# dac-eval-simplified.net
KiCad netlist of a schematic drawn in EAGLE
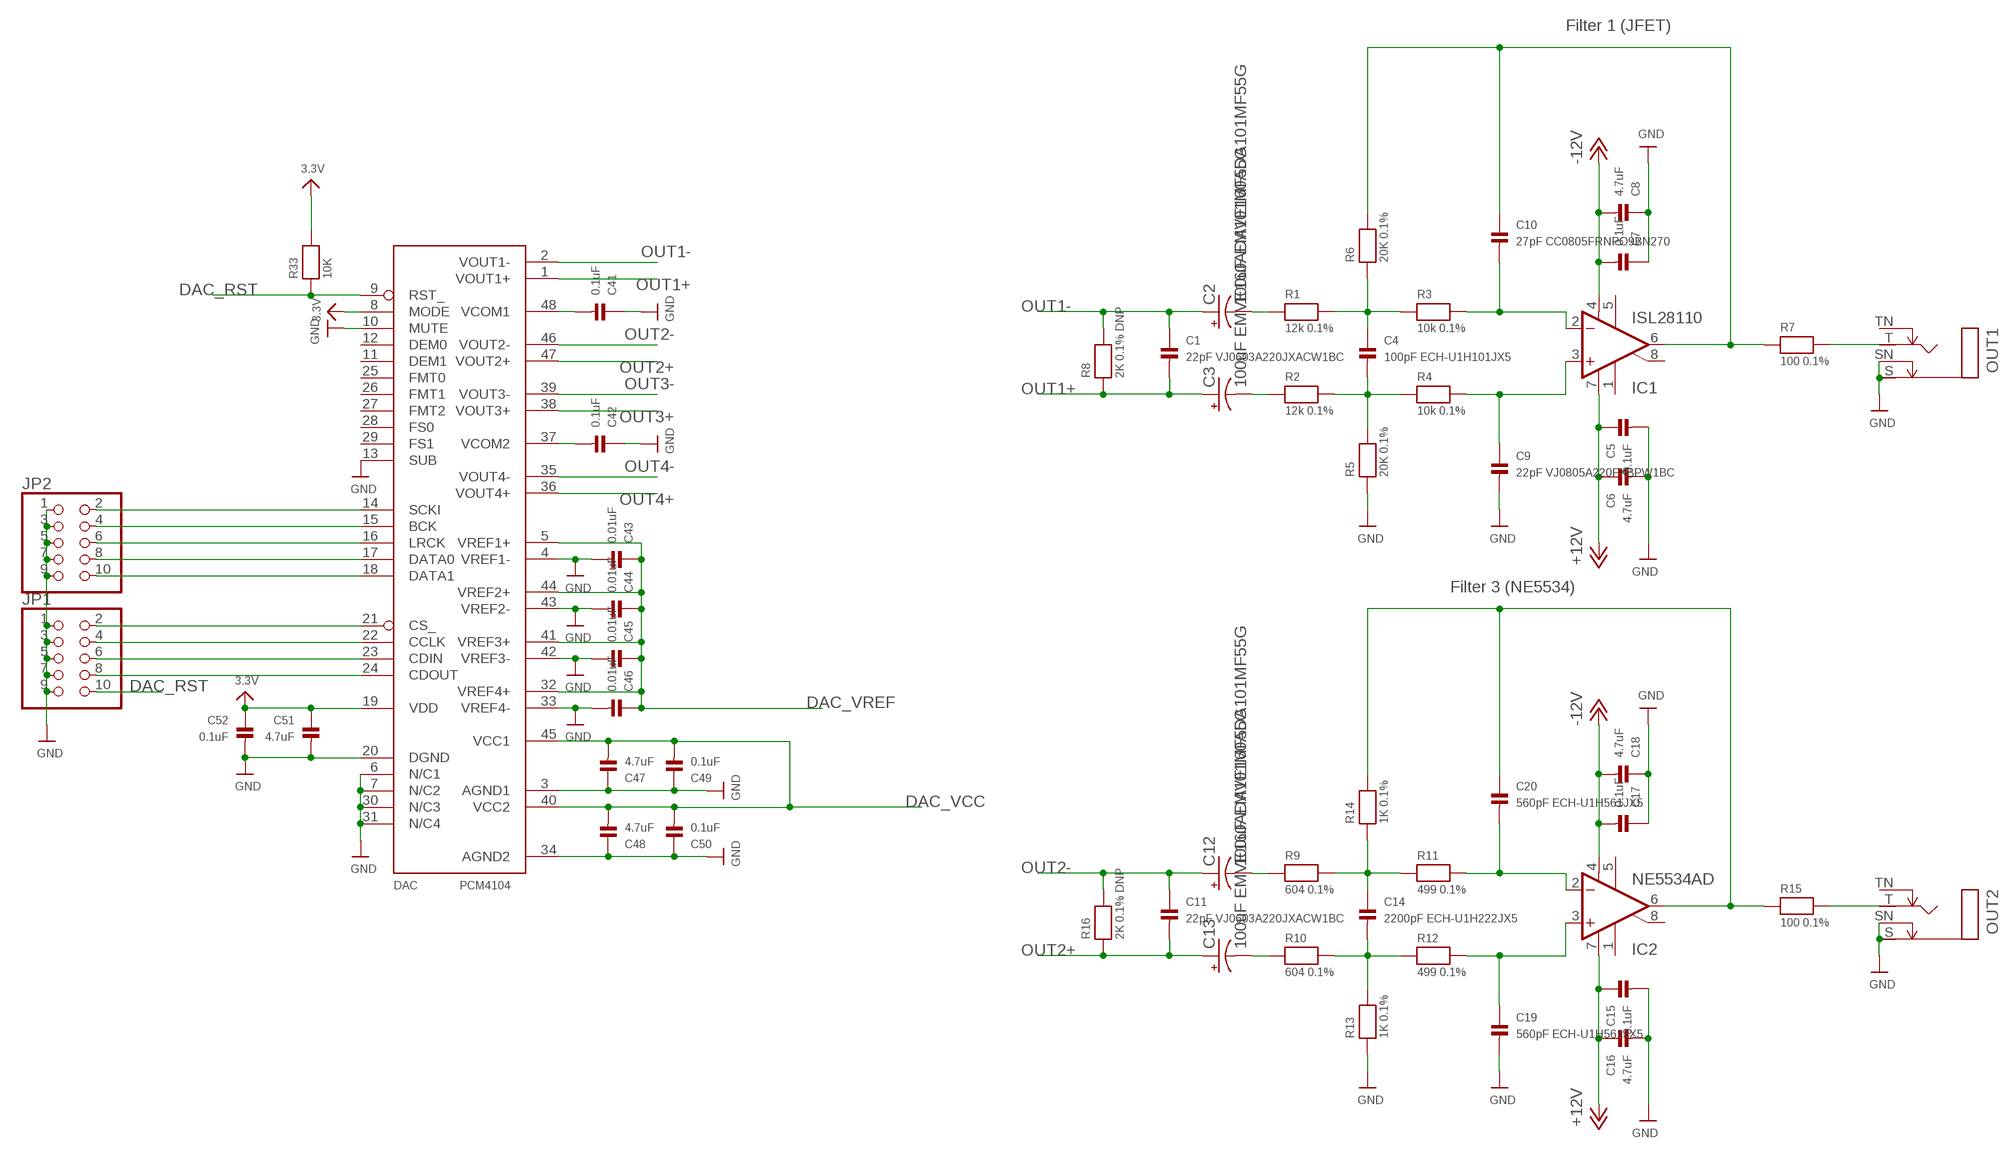
[diagram p0: schematic, sheet 1, part 1 of 2]
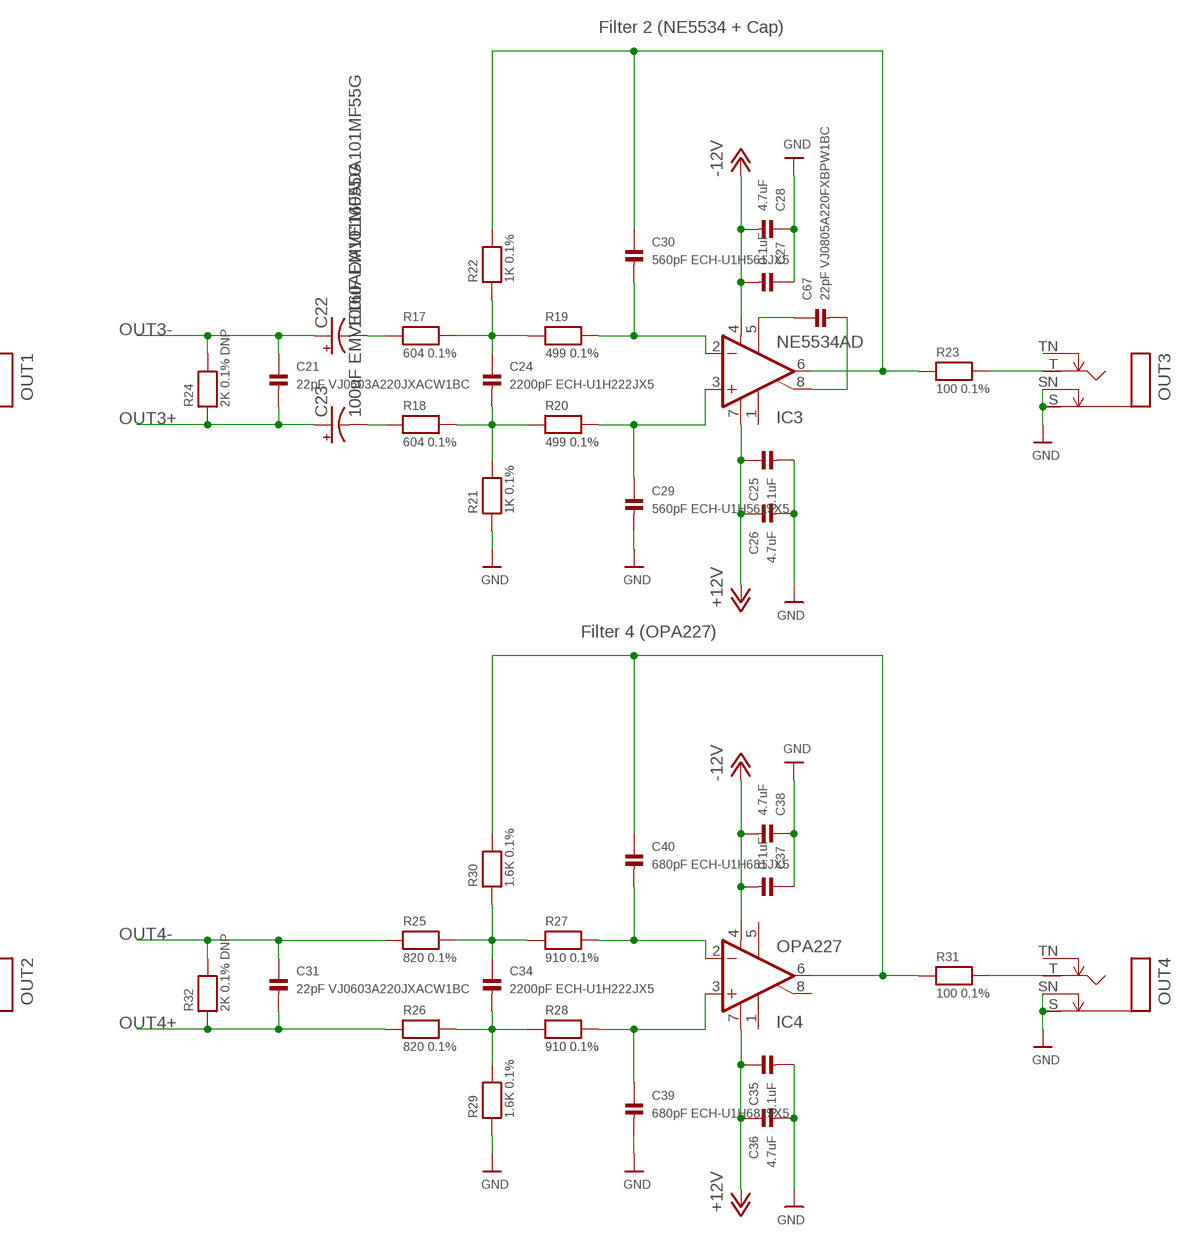
[diagram p1: schematic, sheet 1, part 2 of 2]
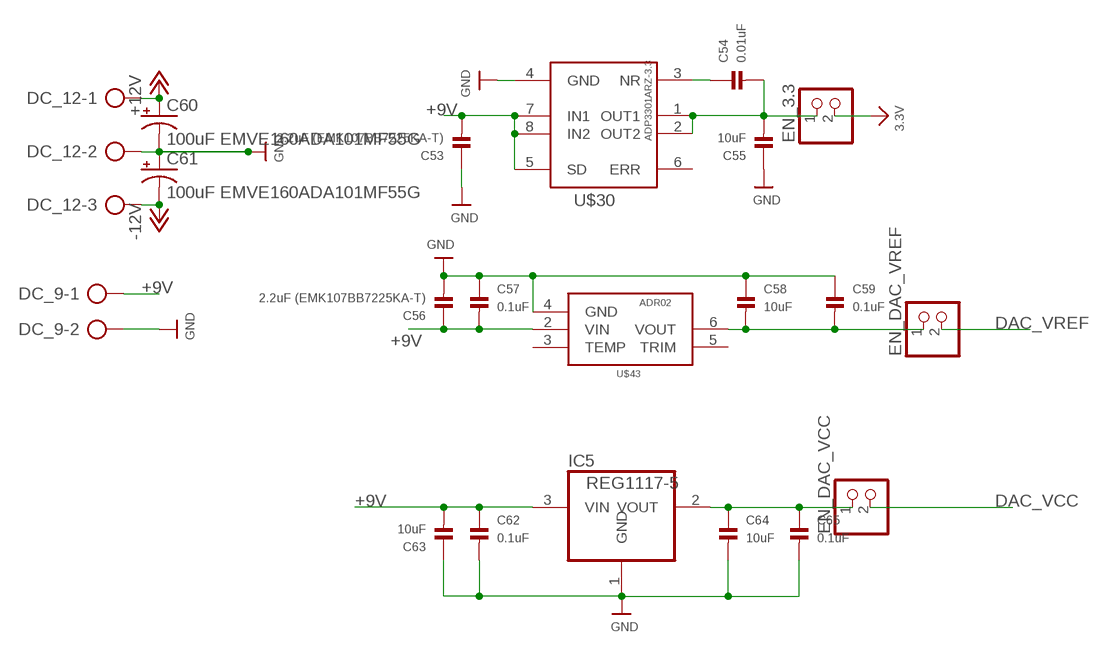
[diagram p2: schematic, sheet 2]

(export (version "E")
  (design (tool "Eeschema 10.0.6"))
  (components
    (comp (ref "C1")
      (value "22pF VJ0603A220JXACW1BC")
      (footprint "eagle-import:0603")
      (libsource (lib "eagle-import") (part "CAP_CERAMIC0603"))
    )
    (comp (ref "C2")
      (value "100uF EMVE160ADA101MF55G")
      (footprint "eagle-import:PANASONIC_D")
      (libsource (lib "eagle-import") (part "CAP_POLD"))
    )
    (comp (ref "C3")
      (value "100uF EMVE160ADA101MF55G")
      (footprint "eagle-import:PANASONIC_D")
      (libsource (lib "eagle-import") (part "CAP_POLD"))
    )
    (comp (ref "C4")
      (value "100pF ECH-U1H101JX5")
      (footprint "eagle-import:0805")
      (libsource (lib "eagle-import") (part "CAP_CERAMIC0805"))
    )
    (comp (ref "C5")
      (value "0.1uF")
      (footprint "eagle-import:0603")
      (libsource (lib "eagle-import") (part "CAP_CERAMIC0603"))
    )
    (comp (ref "C6")
      (value "4.7uF")
      (footprint "eagle-import:0603")
      (libsource (lib "eagle-import") (part "CAP_CERAMIC0603"))
    )
    (comp (ref "C7")
      (value "0.1uF")
      (footprint "eagle-import:0603")
      (libsource (lib "eagle-import") (part "CAP_CERAMIC0603"))
    )
    (comp (ref "C8")
      (value "4.7uF")
      (footprint "eagle-import:0603")
      (libsource (lib "eagle-import") (part "CAP_CERAMIC0603"))
    )
    (comp (ref "C9")
      (value "22pF VJ0805A220FXBPW1BC")
      (footprint "eagle-import:0805")
      (libsource (lib "eagle-import") (part "CAP_CERAMIC0805"))
    )
    (comp (ref "C10")
      (value "27pF CC0805FRNPO9BN270")
      (footprint "eagle-import:0805")
      (libsource (lib "eagle-import") (part "CAP_CERAMIC0805"))
    )
    (comp (ref "C11")
      (value "22pF VJ0603A220JXACW1BC")
      (footprint "eagle-import:0603")
      (libsource (lib "eagle-import") (part "CAP_CERAMIC0603"))
    )
    (comp (ref "C12")
      (value "100uF EMVE160ADA101MF55G")
      (footprint "eagle-import:PANASONIC_D")
      (libsource (lib "eagle-import") (part "CAP_POLD"))
    )
    (comp (ref "C13")
      (value "100uF EMVE160ADA101MF55G")
      (footprint "eagle-import:PANASONIC_D")
      (libsource (lib "eagle-import") (part "CAP_POLD"))
    )
    (comp (ref "C14")
      (value "2200pF ECH-U1H222JX5")
      (footprint "eagle-import:0805")
      (libsource (lib "eagle-import") (part "CAP_CERAMIC0805"))
    )
    (comp (ref "C15")
      (value "0.1uF")
      (footprint "eagle-import:0603")
      (libsource (lib "eagle-import") (part "CAP_CERAMIC0603"))
    )
    (comp (ref "C16")
      (value "4.7uF")
      (footprint "eagle-import:0603")
      (libsource (lib "eagle-import") (part "CAP_CERAMIC0603"))
    )
    (comp (ref "C17")
      (value "0.1uF")
      (footprint "eagle-import:0603")
      (libsource (lib "eagle-import") (part "CAP_CERAMIC0603"))
    )
    (comp (ref "C18")
      (value "4.7uF")
      (footprint "eagle-import:0603")
      (libsource (lib "eagle-import") (part "CAP_CERAMIC0603"))
    )
    (comp (ref "C19")
      (value "560pF ECH-U1H561JX5")
      (footprint "eagle-import:0805")
      (libsource (lib "eagle-import") (part "CAP_CERAMIC0805"))
    )
    (comp (ref "C20")
      (value "560pF ECH-U1H561JX5")
      (footprint "eagle-import:0805")
      (libsource (lib "eagle-import") (part "CAP_CERAMIC0805"))
    )
    (comp (ref "C21")
      (value "22pF VJ0603A220JXACW1BC")
      (footprint "eagle-import:0603")
      (libsource (lib "eagle-import") (part "CAP_CERAMIC0603"))
    )
    (comp (ref "C22")
      (value "100uF EMVE160ADA101MF55G")
      (footprint "eagle-import:PANASONIC_D")
      (libsource (lib "eagle-import") (part "CAP_POLD"))
    )
    (comp (ref "C23")
      (value "100uF EMVE160ADA101MF55G")
      (footprint "eagle-import:PANASONIC_D")
      (libsource (lib "eagle-import") (part "CAP_POLD"))
    )
    (comp (ref "C24")
      (value "2200pF ECH-U1H222JX5")
      (footprint "eagle-import:0805")
      (libsource (lib "eagle-import") (part "CAP_CERAMIC0805"))
    )
    (comp (ref "C25")
      (value "0.1uF")
      (footprint "eagle-import:0603")
      (libsource (lib "eagle-import") (part "CAP_CERAMIC0603"))
    )
    (comp (ref "C26")
      (value "4.7uF")
      (footprint "eagle-import:0603")
      (libsource (lib "eagle-import") (part "CAP_CERAMIC0603"))
    )
    (comp (ref "C27")
      (value "0.1uF")
      (footprint "eagle-import:0603")
      (libsource (lib "eagle-import") (part "CAP_CERAMIC0603"))
    )
    (comp (ref "C28")
      (value "4.7uF")
      (footprint "eagle-import:0603")
      (libsource (lib "eagle-import") (part "CAP_CERAMIC0603"))
    )
    (comp (ref "C29")
      (value "560pF ECH-U1H561JX5")
      (footprint "eagle-import:0805")
      (libsource (lib "eagle-import") (part "CAP_CERAMIC0805"))
    )
    (comp (ref "C30")
      (value "560pF ECH-U1H561JX5")
      (footprint "eagle-import:0805")
      (libsource (lib "eagle-import") (part "CAP_CERAMIC0805"))
    )
    (comp (ref "C31")
      (value "22pF VJ0603A220JXACW1BC")
      (footprint "eagle-import:0603")
      (libsource (lib "eagle-import") (part "CAP_CERAMIC0603"))
    )
    (comp (ref "C34")
      (value "2200pF ECH-U1H222JX5")
      (footprint "eagle-import:0805")
      (libsource (lib "eagle-import") (part "CAP_CERAMIC0805"))
    )
    (comp (ref "C35")
      (value "0.1uF")
      (footprint "eagle-import:0603")
      (libsource (lib "eagle-import") (part "CAP_CERAMIC0603"))
    )
    (comp (ref "C36")
      (value "4.7uF")
      (footprint "eagle-import:0603")
      (libsource (lib "eagle-import") (part "CAP_CERAMIC0603"))
    )
    (comp (ref "C37")
      (value "0.1uF")
      (footprint "eagle-import:0603")
      (libsource (lib "eagle-import") (part "CAP_CERAMIC0603"))
    )
    (comp (ref "C38")
      (value "4.7uF")
      (footprint "eagle-import:0603")
      (libsource (lib "eagle-import") (part "CAP_CERAMIC0603"))
    )
    (comp (ref "C39")
      (value "680pF ECH-U1H681JX5")
      (footprint "eagle-import:0805")
      (libsource (lib "eagle-import") (part "CAP_CERAMIC0805"))
    )
    (comp (ref "C40")
      (value "680pF ECH-U1H681JX5")
      (footprint "eagle-import:0805")
      (libsource (lib "eagle-import") (part "CAP_CERAMIC0805"))
    )
    (comp (ref "C41")
      (value "0.1uF")
      (footprint "eagle-import:0603")
      (libsource (lib "eagle-import") (part "CAP_CERAMIC0603"))
    )
    (comp (ref "C42")
      (value "0.1uF")
      (footprint "eagle-import:0603")
      (libsource (lib "eagle-import") (part "CAP_CERAMIC0603"))
    )
    (comp (ref "C43")
      (value "0.01uF")
      (footprint "eagle-import:0603")
      (libsource (lib "eagle-import") (part "CAP_CERAMIC0603"))
    )
    (comp (ref "C44")
      (value "0.01uF")
      (footprint "eagle-import:0603")
      (libsource (lib "eagle-import") (part "CAP_CERAMIC0603"))
    )
    (comp (ref "C45")
      (value "0.01uF")
      (footprint "eagle-import:0603")
      (libsource (lib "eagle-import") (part "CAP_CERAMIC0603"))
    )
    (comp (ref "C46")
      (value "0.01uF")
      (footprint "eagle-import:0603")
      (libsource (lib "eagle-import") (part "CAP_CERAMIC0603"))
    )
    (comp (ref "C47")
      (value "4.7uF")
      (footprint "eagle-import:0603")
      (libsource (lib "eagle-import") (part "CAP_CERAMIC0603"))
    )
    (comp (ref "C48")
      (value "4.7uF")
      (footprint "eagle-import:0603")
      (libsource (lib "eagle-import") (part "CAP_CERAMIC0603"))
    )
    (comp (ref "C49")
      (value "0.1uF")
      (footprint "eagle-import:0603")
      (libsource (lib "eagle-import") (part "CAP_CERAMIC0603"))
    )
    (comp (ref "C50")
      (value "0.1uF")
      (footprint "eagle-import:0603")
      (libsource (lib "eagle-import") (part "CAP_CERAMIC0603"))
    )
    (comp (ref "C51")
      (value "4.7uF")
      (footprint "eagle-import:0603")
      (libsource (lib "eagle-import") (part "CAP_CERAMIC0603"))
    )
    (comp (ref "C52")
      (value "0.1uF")
      (footprint "eagle-import:0603")
      (libsource (lib "eagle-import") (part "CAP_CERAMIC0603"))
    )
    (comp (ref "C67")
      (value "22pF VJ0805A220FXBPW1BC")
      (footprint "eagle-import:0805")
      (libsource (lib "eagle-import") (part "CAP_CERAMIC0805"))
    )
    (comp (ref "DAC")
      (value "PCM4104")
      (footprint "eagle-import:SQFP-S-7X7-48")
      (libsource (lib "eagle-import") (part "PCM4104"))
    )
    (comp (ref "IC1")
      (value "ISL28110")
      (footprint "eagle-import:SO08")
      (libsource (lib "eagle-import") (part "NE5534DA"))
    )
    (comp (ref "IC2")
      (value "NE5534AD")
      (footprint "eagle-import:SO08")
      (libsource (lib "eagle-import") (part "NE5534DA"))
    )
    (comp (ref "IC3")
      (value "NE5534AD")
      (footprint "eagle-import:SO08")
      (libsource (lib "eagle-import") (part "NE5534DA"))
    )
    (comp (ref "IC4")
      (value "OPA227")
      (footprint "eagle-import:SO08")
      (libsource (lib "eagle-import") (part "NE5534DA"))
    )
    (comp (ref "JP1")
      (value "HEADER-2X5")
      (footprint "eagle-import:2X05")
      (libsource (lib "eagle-import") (part "HEADER-2X5"))
    )
    (comp (ref "JP2")
      (value "HEADER-2X5")
      (footprint "eagle-import:2X05")
      (libsource (lib "eagle-import") (part "HEADER-2X5"))
    )
    (comp (ref "OUT1")
      (value "NMJ4HFD2")
      (footprint "eagle-import:NMJ4HC-S")
      (libsource (lib "eagle-import") (part "MONOSWS"))
    )
    (comp (ref "OUT2")
      (value "NMJ4HFD2")
      (footprint "eagle-import:NMJ4HC-S")
      (libsource (lib "eagle-import") (part "MONOSWS"))
    )
    (comp (ref "OUT3")
      (value "NMJ4HFD2")
      (footprint "eagle-import:NMJ4HC-S")
      (libsource (lib "eagle-import") (part "MONOSWS"))
    )
    (comp (ref "OUT4")
      (value "NMJ4HFD2")
      (footprint "eagle-import:NMJ4HC-S")
      (libsource (lib "eagle-import") (part "MONOSWS"))
    )
    (comp (ref "R1")
      (value "12k 0.1%")
      (footprint "eagle-import:0603")
      (libsource (lib "eagle-import") (part "RESISTOR0603"))
    )
    (comp (ref "R2")
      (value "12k 0.1%")
      (footprint "eagle-import:0603")
      (libsource (lib "eagle-import") (part "RESISTOR0603"))
    )
    (comp (ref "R3")
      (value "10k 0.1%")
      (footprint "eagle-import:0603")
      (libsource (lib "eagle-import") (part "RESISTOR0603"))
    )
    (comp (ref "R4")
      (value "10k 0.1%")
      (footprint "eagle-import:0603")
      (libsource (lib "eagle-import") (part "RESISTOR0603"))
    )
    (comp (ref "R5")
      (value "20K 0.1%")
      (footprint "eagle-import:0603")
      (libsource (lib "eagle-import") (part "RESISTOR0603"))
    )
    (comp (ref "R6")
      (value "20K 0.1%")
      (footprint "eagle-import:0603")
      (libsource (lib "eagle-import") (part "RESISTOR0603"))
    )
    (comp (ref "R7")
      (value "100 0.1%")
      (footprint "eagle-import:0603")
      (libsource (lib "eagle-import") (part "RESISTOR0603"))
    )
    (comp (ref "R8")
      (value "2K 0.1% DNP")
      (footprint "eagle-import:0603")
      (libsource (lib "eagle-import") (part "RESISTOR0603"))
    )
    (comp (ref "R9")
      (value "604 0.1%")
      (footprint "eagle-import:0603")
      (libsource (lib "eagle-import") (part "RESISTOR0603"))
    )
    (comp (ref "R10")
      (value "604 0.1%")
      (footprint "eagle-import:0603")
      (libsource (lib "eagle-import") (part "RESISTOR0603"))
    )
    (comp (ref "R11")
      (value "499 0.1%")
      (footprint "eagle-import:0603")
      (libsource (lib "eagle-import") (part "RESISTOR0603"))
    )
    (comp (ref "R12")
      (value "499 0.1%")
      (footprint "eagle-import:0603")
      (libsource (lib "eagle-import") (part "RESISTOR0603"))
    )
    (comp (ref "R13")
      (value "1K 0.1%")
      (footprint "eagle-import:0603")
      (libsource (lib "eagle-import") (part "RESISTOR0603"))
    )
    (comp (ref "R14")
      (value "1K 0.1%")
      (footprint "eagle-import:0603")
      (libsource (lib "eagle-import") (part "RESISTOR0603"))
    )
    (comp (ref "R15")
      (value "100 0.1%")
      (footprint "eagle-import:0603")
      (libsource (lib "eagle-import") (part "RESISTOR0603"))
    )
    (comp (ref "R16")
      (value "2K 0.1% DNP")
      (footprint "eagle-import:0603")
      (libsource (lib "eagle-import") (part "RESISTOR0603"))
    )
    (comp (ref "R17")
      (value "604 0.1%")
      (footprint "eagle-import:0603")
      (libsource (lib "eagle-import") (part "RESISTOR0603"))
    )
    (comp (ref "R18")
      (value "604 0.1%")
      (footprint "eagle-import:0603")
      (libsource (lib "eagle-import") (part "RESISTOR0603"))
    )
    (comp (ref "R19")
      (value "499 0.1%")
      (footprint "eagle-import:0603")
      (libsource (lib "eagle-import") (part "RESISTOR0603"))
    )
    (comp (ref "R20")
      (value "499 0.1%")
      (footprint "eagle-import:0603")
      (libsource (lib "eagle-import") (part "RESISTOR0603"))
    )
    (comp (ref "R21")
      (value "1K 0.1%")
      (footprint "eagle-import:0603")
      (libsource (lib "eagle-import") (part "RESISTOR0603"))
    )
    (comp (ref "R22")
      (value "1K 0.1%")
      (footprint "eagle-import:0603")
      (libsource (lib "eagle-import") (part "RESISTOR0603"))
    )
    (comp (ref "R23")
      (value "100 0.1%")
      (footprint "eagle-import:0603")
      (libsource (lib "eagle-import") (part "RESISTOR0603"))
    )
    (comp (ref "R24")
      (value "2K 0.1% DNP")
      (footprint "eagle-import:0603")
      (libsource (lib "eagle-import") (part "RESISTOR0603"))
    )
    (comp (ref "R25")
      (value "820 0.1%")
      (footprint "eagle-import:0603")
      (libsource (lib "eagle-import") (part "RESISTOR0603"))
    )
    (comp (ref "R26")
      (value "820 0.1%")
      (footprint "eagle-import:0603")
      (libsource (lib "eagle-import") (part "RESISTOR0603"))
    )
    (comp (ref "R27")
      (value "910 0.1%")
      (footprint "eagle-import:0603")
      (libsource (lib "eagle-import") (part "RESISTOR0603"))
    )
    (comp (ref "R28")
      (value "910 0.1%")
      (footprint "eagle-import:0603")
      (libsource (lib "eagle-import") (part "RESISTOR0603"))
    )
    (comp (ref "R29")
      (value "1.6K 0.1%")
      (footprint "eagle-import:0603")
      (libsource (lib "eagle-import") (part "RESISTOR0603"))
    )
    (comp (ref "R30")
      (value "1.6K 0.1%")
      (footprint "eagle-import:0603")
      (libsource (lib "eagle-import") (part "RESISTOR0603"))
    )
    (comp (ref "R31")
      (value "100 0.1%")
      (footprint "eagle-import:0603")
      (libsource (lib "eagle-import") (part "RESISTOR0603"))
    )
    (comp (ref "R32")
      (value "2K 0.1% DNP")
      (footprint "eagle-import:0603")
      (libsource (lib "eagle-import") (part "RESISTOR0603"))
    )
    (comp (ref "R33")
      (value "10K")
      (footprint "eagle-import:0603")
      (libsource (lib "eagle-import") (part "RESISTOR0603"))
    )
    (comp (ref "C53")
      (value "2.2uF (EMK107BB7225KA-T)")
      (footprint "eagle-import:0603")
      (libsource (lib "eagle-import") (part "CAP_CERAMIC0603"))
    )
    (comp (ref "C54")
      (value "0.01uF")
      (footprint "eagle-import:0603")
      (libsource (lib "eagle-import") (part "CAP_CERAMIC0603"))
    )
    (comp (ref "C55")
      (value "10uF")
      (footprint "eagle-import:0603")
      (libsource (lib "eagle-import") (part "CAP_CERAMIC0603"))
    )
    (comp (ref "C56")
      (value "2.2uF (EMK107BB7225KA-T)")
      (footprint "eagle-import:0603")
      (libsource (lib "eagle-import") (part "CAP_CERAMIC0603"))
    )
    (comp (ref "C57")
      (value "0.1uF")
      (footprint "eagle-import:0603")
      (libsource (lib "eagle-import") (part "CAP_CERAMIC0603"))
    )
    (comp (ref "C58")
      (value "10uF")
      (footprint "eagle-import:0603")
      (libsource (lib "eagle-import") (part "CAP_CERAMIC0603"))
    )
    (comp (ref "C59")
      (value "0.1uF")
      (footprint "eagle-import:0603")
      (libsource (lib "eagle-import") (part "CAP_CERAMIC0603"))
    )
    (comp (ref "C60")
      (value "100uF EMVE160ADA101MF55G")
      (footprint "eagle-import:PANASONIC_D")
      (libsource (lib "eagle-import") (part "CAP_POLD"))
    )
    (comp (ref "C61")
      (value "100uF EMVE160ADA101MF55G")
      (footprint "eagle-import:PANASONIC_D")
      (libsource (lib "eagle-import") (part "CAP_POLD"))
    )
    (comp (ref "C62")
      (value "0.1uF")
      (footprint "eagle-import:0603")
      (libsource (lib "eagle-import") (part "CAP_CERAMIC0603"))
    )
    (comp (ref "C63")
      (value "10uF")
      (footprint "eagle-import:0603")
      (libsource (lib "eagle-import") (part "CAP_CERAMIC0603"))
    )
    (comp (ref "C64")
      (value "10uF")
      (footprint "eagle-import:0603")
      (libsource (lib "eagle-import") (part "CAP_CERAMIC0603"))
    )
    (comp (ref "C65")
      (value "0.1uF")
      (footprint "eagle-import:0603")
      (libsource (lib "eagle-import") (part "CAP_CERAMIC0603"))
    )
    (comp (ref "DC_9")
      (value "AK500/2")
      (footprint "eagle-import:AK500_2")
      (libsource (lib "eagle-import") (part "AK500/2"))
    )
    (comp (ref "DC_12")
      (value "AK500/3")
      (footprint "eagle-import:AK500_3")
      (libsource (lib "eagle-import") (part "AK500/3"))
    )
    (comp (ref "EN_3.3")
      (value "HEADER-1X2")
      (footprint "eagle-import:1X02_OVAL")
      (libsource (lib "eagle-import") (part "HEADER-1X2"))
    )
    (comp (ref "EN_DAC_VCC")
      (value "HEADER-1X2")
      (footprint "eagle-import:1X02_OVAL")
      (libsource (lib "eagle-import") (part "HEADER-1X2"))
    )
    (comp (ref "EN_DAC_VREF")
      (value "HEADER-1X2")
      (footprint "eagle-import:1X02_OVAL")
      (libsource (lib "eagle-import") (part "HEADER-1X2"))
    )
    (comp (ref "IC5")
      (value "REG1117-5")
      (footprint "eagle-import:SOT223")
      (fields (field (name "MPN") "REG1117"))
      (libsource (lib "eagle-import") (part "REG1117"))
    )
    (comp (ref "U$30")
      (value "ADP3301ARZ-3.3")
      (footprint "eagle-import:SO08")
      (libsource (lib "eagle-import") (part "ADP3301"))
    )
    (comp (ref "U$43")
      (value "ADR02")
      (footprint "eagle-import:SOIC8")
      (libsource (lib "eagle-import") (part "ADR02"))
    )
  )
  (nets
    (net (code "1") (name "+9V") (class "Default")
      (node (ref "C53") (pin "2") (pinfunction "P$2_2") (pintype "passive"))
      (node (ref "C56") (pin "1") (pinfunction "P$1_1") (pintype "passive"))
      (node (ref "C57") (pin "2") (pinfunction "P$2_2") (pintype "passive"))
      (node (ref "C62") (pin "1") (pinfunction "P$1_1") (pintype "passive"))
      (node (ref "C63") (pin "2") (pinfunction "P$2_2") (pintype "passive"))
      (node (ref "DC_9") (pin "1") (pinfunction "KL_1") (pintype "passive"))
      (node (ref "IC5") (pin "3") (pinfunction "VIN_3") (pintype "input"))
      (node (ref "U$30") (pin "5") (pinfunction "SD_5") (pintype "bidirectional"))
      (node (ref "U$30") (pin "7") (pinfunction "IN1_7") (pintype "bidirectional"))
      (node (ref "U$30") (pin "8") (pinfunction "IN2_8") (pintype "bidirectional"))
      (node (ref "U$43") (pin "2") (pinfunction "VIN_2") (pintype "bidirectional"))
    )
    (net (code "2") (name "+12V") (class "Default")
      (node (ref "C15") (pin "1") (pinfunction "P$1_1") (pintype "passive"))
      (node (ref "C16") (pin "1") (pinfunction "P$1_1") (pintype "passive"))
      (node (ref "C25") (pin "1") (pinfunction "P$1_1") (pintype "passive"))
      (node (ref "C26") (pin "1") (pinfunction "P$1_1") (pintype "passive"))
      (node (ref "C35") (pin "1") (pinfunction "P$1_1") (pintype "passive"))
      (node (ref "C36") (pin "1") (pinfunction "P$1_1") (pintype "passive"))
      (node (ref "C5") (pin "1") (pinfunction "P$1_1") (pintype "passive"))
      (node (ref "C6") (pin "1") (pinfunction "P$1_1") (pintype "passive"))
      (node (ref "C60") (pin "+") (pinfunction "+_+") (pintype "passive"))
      (node (ref "DC_12") (pin "1") (pinfunction "KL_1") (pintype "passive"))
      (node (ref "IC1") (pin "7") (pinfunction "V+_7") (pintype "power_in"))
      (node (ref "IC2") (pin "7") (pinfunction "V+_7") (pintype "power_in"))
      (node (ref "IC3") (pin "7") (pinfunction "V+_7") (pintype "power_in"))
      (node (ref "IC4") (pin "7") (pinfunction "V+_7") (pintype "power_in"))
    )
    (net (code "3") (name "-12V") (class "Default")
      (node (ref "C17") (pin "2") (pinfunction "P$2_2") (pintype "passive"))
      (node (ref "C18") (pin "2") (pinfunction "P$2_2") (pintype "passive"))
      (node (ref "C27") (pin "2") (pinfunction "P$2_2") (pintype "passive"))
      (node (ref "C28") (pin "2") (pinfunction "P$2_2") (pintype "passive"))
      (node (ref "C37") (pin "2") (pinfunction "P$2_2") (pintype "passive"))
      (node (ref "C38") (pin "2") (pinfunction "P$2_2") (pintype "passive"))
      (node (ref "C61") (pin "-") (pinfunction "-_-") (pintype "passive"))
      (node (ref "C7") (pin "2") (pinfunction "P$2_2") (pintype "passive"))
      (node (ref "C8") (pin "2") (pinfunction "P$2_2") (pintype "passive"))
      (node (ref "DC_12") (pin "3") (pinfunction "KL_3") (pintype "passive"))
      (node (ref "IC1") (pin "4") (pinfunction "V-_4") (pintype "power_in"))
      (node (ref "IC2") (pin "4") (pinfunction "V-_4") (pintype "power_in"))
      (node (ref "IC3") (pin "4") (pinfunction "V-_4") (pintype "power_in"))
      (node (ref "IC4") (pin "4") (pinfunction "V-_4") (pintype "power_in"))
    )
    (net (code "4") (name "3.3V") (class "Default")
      (node (ref "C51") (pin "1") (pinfunction "P$1_1") (pintype "passive"))
      (node (ref "C52") (pin "1") (pinfunction "P$1_1") (pintype "passive"))
      (node (ref "DAC") (pin "19") (pinfunction "VDD_19") (pintype "power_in"))
      (node (ref "DAC") (pin "8") (pinfunction "MODE_8") (pintype "input"))
      (node (ref "EN_3.3") (pin "2") (pinfunction "2_2") (pintype "passive"))
      (node (ref "R33") (pin "2") (pinfunction "2_2") (pintype "passive"))
    )
    (net (code "5") (name "DAC_RST") (class "Default")
      (node (ref "DAC") (pin "9") (pinfunction "RST__9") (pintype "input"))
      (node (ref "JP1") (pin "10") (pinfunction "10_10") (pintype "passive"))
      (node (ref "R33") (pin "1") (pinfunction "1_1") (pintype "passive"))
    )
    (net (code "6") (name "DAC_VCC") (class "Default")
      (node (ref "C47") (pin "2") (pinfunction "P$2_2") (pintype "passive"))
      (node (ref "C48") (pin "2") (pinfunction "P$2_2") (pintype "passive"))
      (node (ref "C49") (pin "2") (pinfunction "P$2_2") (pintype "passive"))
      (node (ref "C50") (pin "2") (pinfunction "P$2_2") (pintype "passive"))
      (node (ref "DAC") (pin "40") (pinfunction "VCC2_40") (pintype "bidirectional"))
      (node (ref "DAC") (pin "45") (pinfunction "VCC1_45") (pintype "bidirectional"))
      (node (ref "EN_DAC_VCC") (pin "2") (pinfunction "2_2") (pintype "passive"))
    )
    (net (code "7") (name "DAC_VREF") (class "Default")
      (node (ref "C43") (pin "1") (pinfunction "P$1_1") (pintype "passive"))
      (node (ref "C44") (pin "1") (pinfunction "P$1_1") (pintype "passive"))
      (node (ref "C45") (pin "1") (pinfunction "P$1_1") (pintype "passive"))
      (node (ref "C46") (pin "1") (pinfunction "P$1_1") (pintype "passive"))
      (node (ref "DAC") (pin "32") (pinfunction "VREF4+_32") (pintype "input"))
      (node (ref "DAC") (pin "41") (pinfunction "VREF3+_41") (pintype "bidirectional"))
      (node (ref "DAC") (pin "44") (pinfunction "VREF2+_44") (pintype "bidirectional"))
      (node (ref "DAC") (pin "5") (pinfunction "VREF1+_5") (pintype "input"))
      (node (ref "EN_DAC_VREF") (pin "2") (pinfunction "2_2") (pintype "passive"))
    )
    (net (code "8") (name "GND") (class "Default")
      (node (ref "C15") (pin "2") (pinfunction "P$2_2") (pintype "passive"))
      (node (ref "C16") (pin "2") (pinfunction "P$2_2") (pintype "passive"))
      (node (ref "C17") (pin "1") (pinfunction "P$1_1") (pintype "passive"))
      (node (ref "C18") (pin "1") (pinfunction "P$1_1") (pintype "passive"))
      (node (ref "C19") (pin "2") (pinfunction "P$2_2") (pintype "passive"))
      (node (ref "C25") (pin "2") (pinfunction "P$2_2") (pintype "passive"))
      (node (ref "C26") (pin "2") (pinfunction "P$2_2") (pintype "passive"))
      (node (ref "C27") (pin "1") (pinfunction "P$1_1") (pintype "passive"))
      (node (ref "C28") (pin "1") (pinfunction "P$1_1") (pintype "passive"))
      (node (ref "C29") (pin "2") (pinfunction "P$2_2") (pintype "passive"))
      (node (ref "C35") (pin "2") (pinfunction "P$2_2") (pintype "passive"))
      (node (ref "C36") (pin "2") (pinfunction "P$2_2") (pintype "passive"))
      (node (ref "C37") (pin "1") (pinfunction "P$1_1") (pintype "passive"))
      (node (ref "C38") (pin "1") (pinfunction "P$1_1") (pintype "passive"))
      (node (ref "C39") (pin "2") (pinfunction "P$2_2") (pintype "passive"))
      (node (ref "C41") (pin "1") (pinfunction "P$1_1") (pintype "passive"))
      (node (ref "C42") (pin "1") (pinfunction "P$1_1") (pintype "passive"))
      (node (ref "C43") (pin "2") (pinfunction "P$2_2") (pintype "passive"))
      (node (ref "C44") (pin "2") (pinfunction "P$2_2") (pintype "passive"))
      (node (ref "C45") (pin "2") (pinfunction "P$2_2") (pintype "passive"))
      (node (ref "C46") (pin "2") (pinfunction "P$2_2") (pintype "passive"))
      (node (ref "C47") (pin "1") (pinfunction "P$1_1") (pintype "passive"))
      (node (ref "C48") (pin "1") (pinfunction "P$1_1") (pintype "passive"))
      (node (ref "C49") (pin "1") (pinfunction "P$1_1") (pintype "passive"))
      (node (ref "C5") (pin "2") (pinfunction "P$2_2") (pintype "passive"))
      (node (ref "C50") (pin "1") (pinfunction "P$1_1") (pintype "passive"))
      (node (ref "C51") (pin "2") (pinfunction "P$2_2") (pintype "passive"))
      (node (ref "C52") (pin "2") (pinfunction "P$2_2") (pintype "passive"))
      (node (ref "C53") (pin "1") (pinfunction "P$1_1") (pintype "passive"))
      (node (ref "C55") (pin "1") (pinfunction "P$1_1") (pintype "passive"))
      (node (ref "C56") (pin "2") (pinfunction "P$2_2") (pintype "passive"))
      (node (ref "C57") (pin "1") (pinfunction "P$1_1") (pintype "passive"))
      (node (ref "C58") (pin "1") (pinfunction "P$1_1") (pintype "passive"))
      (node (ref "C59") (pin "1") (pinfunction "P$1_1") (pintype "passive"))
      (node (ref "C6") (pin "2") (pinfunction "P$2_2") (pintype "passive"))
      (node (ref "C60") (pin "-") (pinfunction "-_-") (pintype "passive"))
      (node (ref "C61") (pin "+") (pinfunction "+_+") (pintype "passive"))
      (node (ref "C62") (pin "2") (pinfunction "P$2_2") (pintype "passive"))
      (node (ref "C63") (pin "1") (pinfunction "P$1_1") (pintype "passive"))
      (node (ref "C64") (pin "2") (pinfunction "P$2_2") (pintype "passive"))
      (node (ref "C65") (pin "2") (pinfunction "P$2_2") (pintype "passive"))
      (node (ref "C7") (pin "1") (pinfunction "P$1_1") (pintype "passive"))
      (node (ref "C8") (pin "1") (pinfunction "P$1_1") (pintype "passive"))
      (node (ref "C9") (pin "2") (pinfunction "P$2_2") (pintype "passive"))
      (node (ref "DAC") (pin "10") (pinfunction "MUTE_10") (pintype "input"))
      (node (ref "DAC") (pin "13") (pinfunction "SUB_13") (pintype "input"))
      (node (ref "DAC") (pin "20") (pinfunction "DGND_20") (pintype "bidirectional"))
      (node (ref "DAC") (pin "3") (pinfunction "AGND1_3") (pintype "bidirectional"))
      (node (ref "DAC") (pin "30") (pinfunction "N/C3_30") (pintype "bidirectional"))
      (node (ref "DAC") (pin "31") (pinfunction "N/C4_31") (pintype "bidirectional"))
      (node (ref "DAC") (pin "33") (pinfunction "VREF4-_33") (pintype "input"))
      (node (ref "DAC") (pin "34") (pinfunction "AGND2_34") (pintype "bidirectional"))
      (node (ref "DAC") (pin "4") (pinfunction "VREF1-_4") (pintype "input"))
      (node (ref "DAC") (pin "42") (pinfunction "VREF3-_42") (pintype "bidirectional"))
      (node (ref "DAC") (pin "43") (pinfunction "VREF2-_43") (pintype "bidirectional"))
      (node (ref "DAC") (pin "6") (pinfunction "N/C1_6") (pintype "bidirectional"))
      (node (ref "DAC") (pin "7") (pinfunction "N/C2_7") (pintype "bidirectional"))
      (node (ref "DC_12") (pin "2") (pinfunction "KL_2") (pintype "passive"))
      (node (ref "DC_9") (pin "2") (pinfunction "KL_2") (pintype "passive"))
      (node (ref "IC5") (pin "1") (pinfunction "GND_1") (pintype "power_in"))
      (node (ref "JP1") (pin "1") (pinfunction "1_1") (pintype "passive"))
      (node (ref "JP1") (pin "3") (pinfunction "3_3") (pintype "passive"))
      (node (ref "JP1") (pin "5") (pinfunction "5_5") (pintype "passive"))
      (node (ref "JP1") (pin "7") (pinfunction "7_7") (pintype "passive"))
      (node (ref "JP1") (pin "9") (pinfunction "9_9") (pintype "passive"))
      (node (ref "JP2") (pin "1") (pinfunction "1_1") (pintype "passive"))
      (node (ref "JP2") (pin "3") (pinfunction "3_3") (pintype "passive"))
      (node (ref "JP2") (pin "5") (pinfunction "5_5") (pintype "passive"))
      (node (ref "JP2") (pin "7") (pinfunction "7_7") (pintype "passive"))
      (node (ref "JP2") (pin "9") (pinfunction "9_9") (pintype "passive"))
      (node (ref "OUT1") (pin "S") (pinfunction "S_S") (pintype "passive"))
      (node (ref "OUT1") (pin "SN") (pinfunction "SN_SN") (pintype "passive"))
      (node (ref "OUT2") (pin "S") (pinfunction "S_S") (pintype "passive"))
      (node (ref "OUT2") (pin "SN") (pinfunction "SN_SN") (pintype "passive"))
      (node (ref "OUT3") (pin "S") (pinfunction "S_S") (pintype "passive"))
      (node (ref "OUT3") (pin "SN") (pinfunction "SN_SN") (pintype "passive"))
      (node (ref "OUT4") (pin "S") (pinfunction "S_S") (pintype "passive"))
      (node (ref "OUT4") (pin "SN") (pinfunction "SN_SN") (pintype "passive"))
      (node (ref "R13") (pin "1") (pinfunction "1_1") (pintype "passive"))
      (node (ref "R21") (pin "1") (pinfunction "1_1") (pintype "passive"))
      (node (ref "R29") (pin "1") (pinfunction "1_1") (pintype "passive"))
      (node (ref "R5") (pin "1") (pinfunction "1_1") (pintype "passive"))
      (node (ref "U$30") (pin "4") (pinfunction "GND_4") (pintype "bidirectional"))
      (node (ref "U$43") (pin "4") (pinfunction "GND_4") (pintype "bidirectional"))
    )
    (net (code "9") (name "Net-(C2-Pad-)") (class "Default")
      (node (ref "C2") (pin "-") (pinfunction "-_-") (pintype "passive"))
      (node (ref "R1") (pin "1") (pinfunction "1_1") (pintype "passive"))
    )
    (net (code "10") (name "Net-(C3-Pad-)") (class "Default")
      (node (ref "C3") (pin "-") (pinfunction "-_-") (pintype "passive"))
      (node (ref "R2") (pin "1") (pinfunction "1_1") (pintype "passive"))
    )
    (net (code "11") (name "Net-(C4-P$1)") (class "Default")
      (node (ref "C4") (pin "1") (pinfunction "P$1_1") (pintype "passive"))
      (node (ref "R1") (pin "2") (pinfunction "2_2") (pintype "passive"))
      (node (ref "R3") (pin "1") (pinfunction "1_1") (pintype "passive"))
      (node (ref "R6") (pin "1") (pinfunction "1_1") (pintype "passive"))
    )
    (net (code "12") (name "Net-(C4-P$2)") (class "Default")
      (node (ref "C4") (pin "2") (pinfunction "P$2_2") (pintype "passive"))
      (node (ref "R2") (pin "2") (pinfunction "2_2") (pintype "passive"))
      (node (ref "R4") (pin "1") (pinfunction "1_1") (pintype "passive"))
      (node (ref "R5") (pin "2") (pinfunction "2_2") (pintype "passive"))
    )
    (net (code "13") (name "Net-(C9-P$1)") (class "Default")
      (node (ref "C9") (pin "1") (pinfunction "P$1_1") (pintype "passive"))
      (node (ref "IC1") (pin "3") (pinfunction "+IN_3") (pintype "input"))
      (node (ref "R4") (pin "2") (pinfunction "2_2") (pintype "passive"))
    )
    (net (code "14") (name "Net-(C10-P$1)") (class "Default")
      (node (ref "C10") (pin "1") (pinfunction "P$1_1") (pintype "passive"))
      (node (ref "IC1") (pin "6") (pinfunction "OUT_6") (pintype "output"))
      (node (ref "R6") (pin "2") (pinfunction "2_2") (pintype "passive"))
      (node (ref "R7") (pin "1") (pinfunction "1_1") (pintype "passive"))
    )
    (net (code "15") (name "Net-(C10-P$2)") (class "Default")
      (node (ref "C10") (pin "2") (pinfunction "P$2_2") (pintype "passive"))
      (node (ref "IC1") (pin "2") (pinfunction "-IN_2") (pintype "input"))
      (node (ref "R3") (pin "2") (pinfunction "2_2") (pintype "passive"))
    )
    (net (code "16") (name "Net-(C12-Pad-)") (class "Default")
      (node (ref "C12") (pin "-") (pinfunction "-_-") (pintype "passive"))
      (node (ref "R9") (pin "1") (pinfunction "1_1") (pintype "passive"))
    )
    (net (code "17") (name "Net-(C13-Pad-)") (class "Default")
      (node (ref "C13") (pin "-") (pinfunction "-_-") (pintype "passive"))
      (node (ref "R10") (pin "1") (pinfunction "1_1") (pintype "passive"))
    )
    (net (code "18") (name "Net-(C14-P$1)") (class "Default")
      (node (ref "C14") (pin "1") (pinfunction "P$1_1") (pintype "passive"))
      (node (ref "R11") (pin "1") (pinfunction "1_1") (pintype "passive"))
      (node (ref "R14") (pin "1") (pinfunction "1_1") (pintype "passive"))
      (node (ref "R9") (pin "2") (pinfunction "2_2") (pintype "passive"))
    )
    (net (code "19") (name "Net-(C14-P$2)") (class "Default")
      (node (ref "C14") (pin "2") (pinfunction "P$2_2") (pintype "passive"))
      (node (ref "R10") (pin "2") (pinfunction "2_2") (pintype "passive"))
      (node (ref "R12") (pin "1") (pinfunction "1_1") (pintype "passive"))
      (node (ref "R13") (pin "2") (pinfunction "2_2") (pintype "passive"))
    )
    (net (code "20") (name "Net-(C19-P$1)") (class "Default")
      (node (ref "C19") (pin "1") (pinfunction "P$1_1") (pintype "passive"))
      (node (ref "IC2") (pin "3") (pinfunction "+IN_3") (pintype "input"))
      (node (ref "R12") (pin "2") (pinfunction "2_2") (pintype "passive"))
    )
    (net (code "21") (name "Net-(C20-P$1)") (class "Default")
      (node (ref "C20") (pin "1") (pinfunction "P$1_1") (pintype "passive"))
      (node (ref "IC2") (pin "6") (pinfunction "OUT_6") (pintype "output"))
      (node (ref "R14") (pin "2") (pinfunction "2_2") (pintype "passive"))
      (node (ref "R15") (pin "1") (pinfunction "1_1") (pintype "passive"))
    )
    (net (code "22") (name "Net-(C20-P$2)") (class "Default")
      (node (ref "C20") (pin "2") (pinfunction "P$2_2") (pintype "passive"))
      (node (ref "IC2") (pin "2") (pinfunction "-IN_2") (pintype "input"))
      (node (ref "R11") (pin "2") (pinfunction "2_2") (pintype "passive"))
    )
    (net (code "23") (name "Net-(C22-Pad-)") (class "Default")
      (node (ref "C22") (pin "-") (pinfunction "-_-") (pintype "passive"))
      (node (ref "R17") (pin "1") (pinfunction "1_1") (pintype "passive"))
    )
    (net (code "24") (name "Net-(C23-Pad-)") (class "Default")
      (node (ref "C23") (pin "-") (pinfunction "-_-") (pintype "passive"))
      (node (ref "R18") (pin "1") (pinfunction "1_1") (pintype "passive"))
    )
    (net (code "25") (name "Net-(C24-P$1)") (class "Default")
      (node (ref "C24") (pin "1") (pinfunction "P$1_1") (pintype "passive"))
      (node (ref "R17") (pin "2") (pinfunction "2_2") (pintype "passive"))
      (node (ref "R19") (pin "1") (pinfunction "1_1") (pintype "passive"))
      (node (ref "R22") (pin "1") (pinfunction "1_1") (pintype "passive"))
    )
    (net (code "26") (name "Net-(C24-P$2)") (class "Default")
      (node (ref "C24") (pin "2") (pinfunction "P$2_2") (pintype "passive"))
      (node (ref "R18") (pin "2") (pinfunction "2_2") (pintype "passive"))
      (node (ref "R20") (pin "1") (pinfunction "1_1") (pintype "passive"))
      (node (ref "R21") (pin "2") (pinfunction "2_2") (pintype "passive"))
    )
    (net (code "27") (name "Net-(C29-P$1)") (class "Default")
      (node (ref "C29") (pin "1") (pinfunction "P$1_1") (pintype "passive"))
      (node (ref "IC3") (pin "3") (pinfunction "+IN_3") (pintype "input"))
      (node (ref "R20") (pin "2") (pinfunction "2_2") (pintype "passive"))
    )
    (net (code "28") (name "Net-(C30-P$1)") (class "Default")
      (node (ref "C30") (pin "1") (pinfunction "P$1_1") (pintype "passive"))
      (node (ref "IC3") (pin "6") (pinfunction "OUT_6") (pintype "output"))
      (node (ref "R22") (pin "2") (pinfunction "2_2") (pintype "passive"))
      (node (ref "R23") (pin "1") (pinfunction "1_1") (pintype "passive"))
    )
    (net (code "29") (name "Net-(C30-P$2)") (class "Default")
      (node (ref "C30") (pin "2") (pinfunction "P$2_2") (pintype "passive"))
      (node (ref "IC3") (pin "2") (pinfunction "-IN_2") (pintype "input"))
      (node (ref "R19") (pin "2") (pinfunction "2_2") (pintype "passive"))
    )
    (net (code "30") (name "Net-(C34-P$1)") (class "Default")
      (node (ref "C34") (pin "1") (pinfunction "P$1_1") (pintype "passive"))
      (node (ref "R25") (pin "2") (pinfunction "2_2") (pintype "passive"))
      (node (ref "R27") (pin "1") (pinfunction "1_1") (pintype "passive"))
      (node (ref "R30") (pin "1") (pinfunction "1_1") (pintype "passive"))
    )
    (net (code "31") (name "Net-(C34-P$2)") (class "Default")
      (node (ref "C34") (pin "2") (pinfunction "P$2_2") (pintype "passive"))
      (node (ref "R26") (pin "2") (pinfunction "2_2") (pintype "passive"))
      (node (ref "R28") (pin "1") (pinfunction "1_1") (pintype "passive"))
      (node (ref "R29") (pin "2") (pinfunction "2_2") (pintype "passive"))
    )
    (net (code "32") (name "Net-(C39-P$1)") (class "Default")
      (node (ref "C39") (pin "1") (pinfunction "P$1_1") (pintype "passive"))
      (node (ref "IC4") (pin "3") (pinfunction "+IN_3") (pintype "input"))
      (node (ref "R28") (pin "2") (pinfunction "2_2") (pintype "passive"))
    )
    (net (code "33") (name "Net-(C40-P$1)") (class "Default")
      (node (ref "C40") (pin "1") (pinfunction "P$1_1") (pintype "passive"))
      (node (ref "IC4") (pin "6") (pinfunction "OUT_6") (pintype "output"))
      (node (ref "R30") (pin "2") (pinfunction "2_2") (pintype "passive"))
      (node (ref "R31") (pin "1") (pinfunction "1_1") (pintype "passive"))
    )
    (net (code "34") (name "Net-(C40-P$2)") (class "Default")
      (node (ref "C40") (pin "2") (pinfunction "P$2_2") (pintype "passive"))
      (node (ref "IC4") (pin "2") (pinfunction "-IN_2") (pintype "input"))
      (node (ref "R27") (pin "2") (pinfunction "2_2") (pintype "passive"))
    )
    (net (code "35") (name "Net-(C41-P$2)") (class "Default")
      (node (ref "C41") (pin "2") (pinfunction "P$2_2") (pintype "passive"))
      (node (ref "DAC") (pin "48") (pinfunction "VCOM1_48") (pintype "output"))
    )
    (net (code "36") (name "Net-(C42-P$2)") (class "Default")
      (node (ref "C42") (pin "2") (pinfunction "P$2_2") (pintype "passive"))
      (node (ref "DAC") (pin "37") (pinfunction "VCOM2_37") (pintype "output"))
    )
    (net (code "37") (name "Net-(C54-P$1)") (class "Default")
      (node (ref "C54") (pin "1") (pinfunction "P$1_1") (pintype "passive"))
      (node (ref "U$30") (pin "3") (pinfunction "NR_3") (pintype "bidirectional"))
    )
    (net (code "38") (name "Net-(C54-P$2)") (class "Default")
      (node (ref "C54") (pin "2") (pinfunction "P$2_2") (pintype "passive"))
      (node (ref "C55") (pin "2") (pinfunction "P$2_2") (pintype "passive"))
      (node (ref "EN_3.3") (pin "1") (pinfunction "1_1") (pintype "passive"))
      (node (ref "U$30") (pin "1") (pinfunction "OUT1_1") (pintype "bidirectional"))
      (node (ref "U$30") (pin "2") (pinfunction "OUT2_2") (pintype "bidirectional"))
    )
    (net (code "39") (name "Net-(C58-P$2)") (class "Default")
      (node (ref "C58") (pin "2") (pinfunction "P$2_2") (pintype "passive"))
      (node (ref "C59") (pin "2") (pinfunction "P$2_2") (pintype "passive"))
      (node (ref "EN_DAC_VREF") (pin "1") (pinfunction "1_1") (pintype "passive"))
      (node (ref "U$43") (pin "6") (pinfunction "VOUT_6") (pintype "bidirectional"))
    )
    (net (code "40") (name "Net-(C64-P$1)") (class "Default")
      (node (ref "C64") (pin "1") (pinfunction "P$1_1") (pintype "passive"))
      (node (ref "C65") (pin "1") (pinfunction "P$1_1") (pintype "passive"))
      (node (ref "EN_DAC_VCC") (pin "1") (pinfunction "1_1") (pintype "passive"))
      (node (ref "IC5") (pin "2") (pinfunction "VOUT_2") (pintype "output"))
    )
    (net (code "41") (name "Net-(C67-P$1)") (class "Default")
      (node (ref "C67") (pin "1") (pinfunction "P$1_1") (pintype "passive"))
      (node (ref "IC3") (pin "5") (pinfunction "CMP_5") (pintype "passive"))
    )
    (net (code "42") (name "Net-(C67-P$2)") (class "Default")
      (node (ref "C67") (pin "2") (pinfunction "P$2_2") (pintype "passive"))
      (node (ref "IC3") (pin "8") (pinfunction "ON/CMP_8") (pintype "passive"))
    )
    (net (code "43") (name "Net-(DAC-BCK)") (class "Default")
      (node (ref "DAC") (pin "15") (pinfunction "BCK_15") (pintype "input"))
      (node (ref "JP2") (pin "4") (pinfunction "4_4") (pintype "passive"))
    )
    (net (code "44") (name "Net-(DAC-CCLK)") (class "Default")
      (node (ref "DAC") (pin "22") (pinfunction "CCLK_22") (pintype "input"))
      (node (ref "JP1") (pin "4") (pinfunction "4_4") (pintype "passive"))
    )
    (net (code "45") (name "Net-(DAC-CDIN)") (class "Default")
      (node (ref "DAC") (pin "23") (pinfunction "CDIN_23") (pintype "input"))
      (node (ref "JP1") (pin "6") (pinfunction "6_6") (pintype "passive"))
    )
    (net (code "46") (name "Net-(DAC-CDOUT)") (class "Default")
      (node (ref "DAC") (pin "24") (pinfunction "CDOUT_24") (pintype "output"))
      (node (ref "JP1") (pin "8") (pinfunction "8_8") (pintype "passive"))
    )
    (net (code "47") (name "Net-(DAC-CS_)") (class "Default")
      (node (ref "DAC") (pin "21") (pinfunction "CS__21") (pintype "input"))
      (node (ref "JP1") (pin "2") (pinfunction "2_2") (pintype "passive"))
    )
    (net (code "48") (name "Net-(DAC-DATA0)") (class "Default")
      (node (ref "DAC") (pin "17") (pinfunction "DATA0_17") (pintype "input"))
      (node (ref "JP2") (pin "8") (pinfunction "8_8") (pintype "passive"))
    )
    (net (code "49") (name "Net-(DAC-DATA1)") (class "Default")
      (node (ref "DAC") (pin "18") (pinfunction "DATA1_18") (pintype "input"))
      (node (ref "JP2") (pin "10") (pinfunction "10_10") (pintype "passive"))
    )
    (net (code "50") (name "Net-(DAC-LRCK)") (class "Default")
      (node (ref "DAC") (pin "16") (pinfunction "LRCK_16") (pintype "input"))
      (node (ref "JP2") (pin "6") (pinfunction "6_6") (pintype "passive"))
    )
    (net (code "51") (name "Net-(DAC-SCKI)") (class "Default")
      (node (ref "DAC") (pin "14") (pinfunction "SCKI_14") (pintype "input"))
      (node (ref "JP2") (pin "2") (pinfunction "2_2") (pintype "passive"))
    )
    (net (code "52") (name "Net-(OUT1-PadT)") (class "Default")
      (node (ref "OUT1") (pin "T") (pinfunction "T_T") (pintype "passive"))
      (node (ref "R7") (pin "2") (pinfunction "2_2") (pintype "passive"))
    )
    (net (code "53") (name "Net-(OUT2-PadT)") (class "Default")
      (node (ref "OUT2") (pin "T") (pinfunction "T_T") (pintype "passive"))
      (node (ref "R15") (pin "2") (pinfunction "2_2") (pintype "passive"))
    )
    (net (code "54") (name "Net-(OUT3-PadT)") (class "Default")
      (node (ref "OUT3") (pin "T") (pinfunction "T_T") (pintype "passive"))
      (node (ref "R23") (pin "2") (pinfunction "2_2") (pintype "passive"))
    )
    (net (code "55") (name "Net-(OUT4-PadT)") (class "Default")
      (node (ref "OUT4") (pin "T") (pinfunction "T_T") (pintype "passive"))
      (node (ref "R31") (pin "2") (pinfunction "2_2") (pintype "passive"))
    )
    (net (code "56") (name "OUT1+") (class "Default")
      (node (ref "C1") (pin "2") (pinfunction "P$2_2") (pintype "passive"))
      (node (ref "C3") (pin "+") (pinfunction "+_+") (pintype "passive"))
      (node (ref "DAC") (pin "1") (pinfunction "VOUT1+_1") (pintype "output"))
      (node (ref "R8") (pin "1") (pinfunction "1_1") (pintype "passive"))
    )
    (net (code "57") (name "OUT1-") (class "Default")
      (node (ref "C1") (pin "1") (pinfunction "P$1_1") (pintype "passive"))
      (node (ref "C2") (pin "+") (pinfunction "+_+") (pintype "passive"))
      (node (ref "DAC") (pin "2") (pinfunction "VOUT1-_2") (pintype "output"))
      (node (ref "R8") (pin "2") (pinfunction "2_2") (pintype "passive"))
    )
    (net (code "58") (name "OUT2+") (class "Default")
      (node (ref "C11") (pin "2") (pinfunction "P$2_2") (pintype "passive"))
      (node (ref "C13") (pin "+") (pinfunction "+_+") (pintype "passive"))
      (node (ref "DAC") (pin "47") (pinfunction "VOUT2+_47") (pintype "output"))
      (node (ref "R16") (pin "1") (pinfunction "1_1") (pintype "passive"))
    )
    (net (code "59") (name "OUT2-") (class "Default")
      (node (ref "C11") (pin "1") (pinfunction "P$1_1") (pintype "passive"))
      (node (ref "C12") (pin "+") (pinfunction "+_+") (pintype "passive"))
      (node (ref "DAC") (pin "46") (pinfunction "VOUT2-_46") (pintype "output"))
      (node (ref "R16") (pin "2") (pinfunction "2_2") (pintype "passive"))
    )
    (net (code "60") (name "OUT3+") (class "Default")
      (node (ref "C21") (pin "2") (pinfunction "P$2_2") (pintype "passive"))
      (node (ref "C23") (pin "+") (pinfunction "+_+") (pintype "passive"))
      (node (ref "DAC") (pin "38") (pinfunction "VOUT3+_38") (pintype "output"))
      (node (ref "R24") (pin "1") (pinfunction "1_1") (pintype "passive"))
    )
    (net (code "61") (name "OUT3-") (class "Default")
      (node (ref "C21") (pin "1") (pinfunction "P$1_1") (pintype "passive"))
      (node (ref "C22") (pin "+") (pinfunction "+_+") (pintype "passive"))
      (node (ref "DAC") (pin "39") (pinfunction "VOUT3-_39") (pintype "output"))
      (node (ref "R24") (pin "2") (pinfunction "2_2") (pintype "passive"))
    )
    (net (code "62") (name "OUT4+") (class "Default")
      (node (ref "C31") (pin "2") (pinfunction "P$2_2") (pintype "passive"))
      (node (ref "DAC") (pin "36") (pinfunction "VOUT4+_36") (pintype "output"))
      (node (ref "R26") (pin "1") (pinfunction "1_1") (pintype "passive"))
      (node (ref "R32") (pin "1") (pinfunction "1_1") (pintype "passive"))
    )
    (net (code "63") (name "OUT4-") (class "Default")
      (node (ref "C31") (pin "1") (pinfunction "P$1_1") (pintype "passive"))
      (node (ref "DAC") (pin "35") (pinfunction "VOUT4-_35") (pintype "output"))
      (node (ref "R25") (pin "1") (pinfunction "1_1") (pintype "passive"))
      (node (ref "R32") (pin "2") (pinfunction "2_2") (pintype "passive"))
    )
    (net (code "64") (name "unconnected-(DAC-DEM0-Pad12)") (class "Default")
      (node (ref "DAC") (pin "12") (pinfunction "DEM0_12") (pintype "input"))
    )
    (net (code "65") (name "unconnected-(DAC-DEM1-Pad11)") (class "Default")
      (node (ref "DAC") (pin "11") (pinfunction "DEM1_11") (pintype "input"))
    )
    (net (code "66") (name "unconnected-(DAC-FMT0-Pad25)") (class "Default")
      (node (ref "DAC") (pin "25") (pinfunction "FMT0_25") (pintype "input"))
    )
    (net (code "67") (name "unconnected-(DAC-FMT1-Pad26)") (class "Default")
      (node (ref "DAC") (pin "26") (pinfunction "FMT1_26") (pintype "input"))
    )
    (net (code "68") (name "unconnected-(DAC-FMT2-Pad27)") (class "Default")
      (node (ref "DAC") (pin "27") (pinfunction "FMT2_27") (pintype "input"))
    )
    (net (code "69") (name "unconnected-(DAC-FS0-Pad28)") (class "Default")
      (node (ref "DAC") (pin "28") (pinfunction "FS0_28") (pintype "input"))
    )
    (net (code "70") (name "unconnected-(DAC-FS1-Pad29)") (class "Default")
      (node (ref "DAC") (pin "29") (pinfunction "FS1_29") (pintype "input"))
    )
    (net (code "71") (name "unconnected-(IC1-CMP-Pad5)") (class "Default")
      (node (ref "IC1") (pin "5") (pinfunction "CMP_5") (pintype "passive"))
    )
    (net (code "72") (name "unconnected-(IC1-ON-Pad1)") (class "Default")
      (node (ref "IC1") (pin "1") (pinfunction "ON_1") (pintype "passive"))
    )
    (net (code "73") (name "unconnected-(IC1-ON{slash}CMP-Pad8)") (class "Default")
      (node (ref "IC1") (pin "8") (pinfunction "ON/CMP_8") (pintype "passive"))
    )
    (net (code "74") (name "unconnected-(IC2-CMP-Pad5)") (class "Default")
      (node (ref "IC2") (pin "5") (pinfunction "CMP_5") (pintype "passive"))
    )
    (net (code "75") (name "unconnected-(IC2-ON-Pad1)") (class "Default")
      (node (ref "IC2") (pin "1") (pinfunction "ON_1") (pintype "passive"))
    )
    (net (code "76") (name "unconnected-(IC2-ON{slash}CMP-Pad8)") (class "Default")
      (node (ref "IC2") (pin "8") (pinfunction "ON/CMP_8") (pintype "passive"))
    )
    (net (code "77") (name "unconnected-(IC3-ON-Pad1)") (class "Default")
      (node (ref "IC3") (pin "1") (pinfunction "ON_1") (pintype "passive"))
    )
    (net (code "78") (name "unconnected-(IC4-CMP-Pad5)") (class "Default")
      (node (ref "IC4") (pin "5") (pinfunction "CMP_5") (pintype "passive"))
    )
    (net (code "79") (name "unconnected-(IC4-ON-Pad1)") (class "Default")
      (node (ref "IC4") (pin "1") (pinfunction "ON_1") (pintype "passive"))
    )
    (net (code "80") (name "unconnected-(IC4-ON{slash}CMP-Pad8)") (class "Default")
      (node (ref "IC4") (pin "8") (pinfunction "ON/CMP_8") (pintype "passive"))
    )
    (net (code "81") (name "unconnected-(OUT1-PadTN)") (class "Default")
      (node (ref "OUT1") (pin "TN") (pinfunction "TN_TN") (pintype "passive"))
    )
    (net (code "82") (name "unconnected-(OUT2-PadTN)") (class "Default")
      (node (ref "OUT2") (pin "TN") (pinfunction "TN_TN") (pintype "passive"))
    )
    (net (code "83") (name "unconnected-(OUT3-PadTN)") (class "Default")
      (node (ref "OUT3") (pin "TN") (pinfunction "TN_TN") (pintype "passive"))
    )
    (net (code "84") (name "unconnected-(OUT4-PadTN)") (class "Default")
      (node (ref "OUT4") (pin "TN") (pinfunction "TN_TN") (pintype "passive"))
    )
    (net (code "85") (name "unconnected-(U$30-ERR-Pad6)") (class "Default")
      (node (ref "U$30") (pin "6") (pinfunction "ERR_6") (pintype "bidirectional"))
    )
    (net (code "86") (name "unconnected-(U$43-TEMP-Pad3)") (class "Default")
      (node (ref "U$43") (pin "3") (pinfunction "TEMP_3") (pintype "bidirectional"))
    )
    (net (code "87") (name "unconnected-(U$43-TRIM-Pad5)") (class "Default")
      (node (ref "U$43") (pin "5") (pinfunction "TRIM_5") (pintype "bidirectional"))
    )
  )
)
